# SingleBoardDrone_Pow.net
KiCad netlist of a schematic drawn in Altium Designer
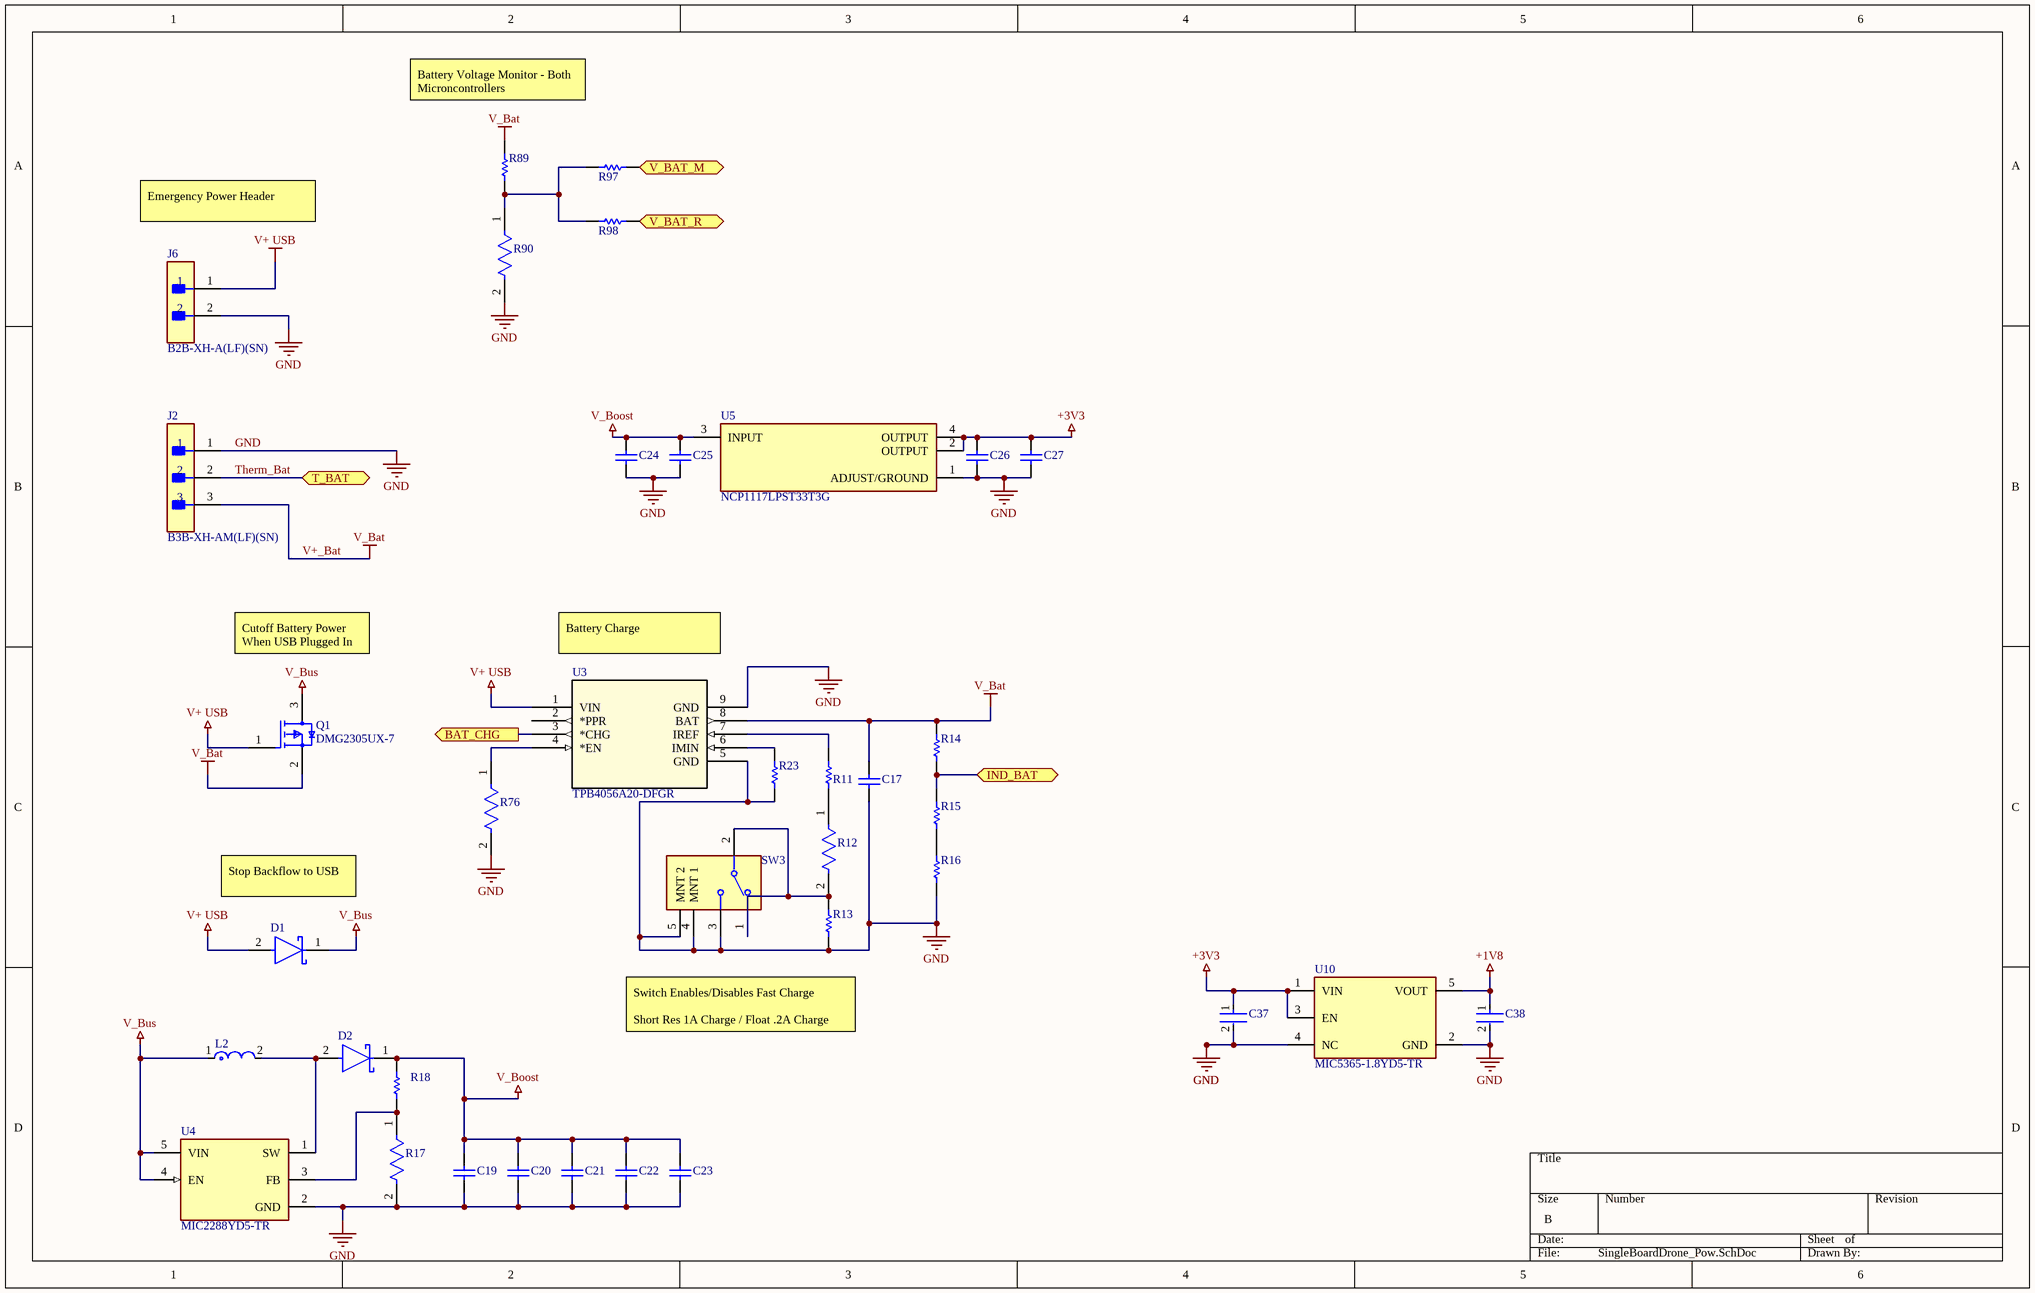
[diagram p0: SingleBoardDrone_Pow.SchDoc]

(export (version "E")
  (design (tool "Eeschema 10.0.6"))
  (components
    (comp (ref "C17")
      (value "CL10A475KQ8NNNC")
      (footprint "CAPC1608X90X30LL10T20")
      (description "Chip Capacitor, 4.7 uF, +/- 10%, 6.3 V, -55 to 85 degC, 0603 (1608 Metric), RoHS, Tape and Reel")
      (fields (field (name "MANUFACTURER") "Samsung Electro-Mechanics"))
      (libsource (lib "Altium Content Vault") (part "CAP-NP-2"))
    )
    (comp (ref "C19")
      (value "CL10A475KQ8NNNC")
      (footprint "CAPC1608X90X30LL10T20")
      (description "Chip Capacitor, 4.7 uF, +/- 10%, 6.3 V, -55 to 85 degC, 0603 (1608 Metric), RoHS, Tape and Reel")
      (fields (field (name "MANUFACTURER") "Samsung Electro-Mechanics"))
      (libsource (lib "Altium Content Vault") (part "CAP-NP-2"))
    )
    (comp (ref "C20")
      (value "CL10A475KQ8NNNC")
      (footprint "CAPC1608X90X30LL10T20")
      (description "Chip Capacitor, 4.7 uF, +/- 10%, 6.3 V, -55 to 85 degC, 0603 (1608 Metric), RoHS, Tape and Reel")
      (fields (field (name "MANUFACTURER") "Samsung Electro-Mechanics"))
      (libsource (lib "Altium Content Vault") (part "CAP-NP-2"))
    )
    (comp (ref "C21")
      (value "CL10A475KQ8NNNC")
      (footprint "CAPC1608X90X30LL10T20")
      (description "Chip Capacitor, 4.7 uF, +/- 10%, 6.3 V, -55 to 85 degC, 0603 (1608 Metric), RoHS, Tape and Reel")
      (fields (field (name "MANUFACTURER") "Samsung Electro-Mechanics"))
      (libsource (lib "Altium Content Vault") (part "CAP-NP-2"))
    )
    (comp (ref "C22")
      (value "CL10A475KQ8NNNC")
      (footprint "CAPC1608X90X30LL10T20")
      (description "Chip Capacitor, 4.7 uF, +/- 10%, 6.3 V, -55 to 85 degC, 0603 (1608 Metric), RoHS, Tape and Reel")
      (fields (field (name "MANUFACTURER") "Samsung Electro-Mechanics"))
      (libsource (lib "Altium Content Vault") (part "CAP-NP-2"))
    )
    (comp (ref "C23")
      (value "CL10A475KQ8NNNC")
      (footprint "CAPC1608X90X30LL10T20")
      (description "Chip Capacitor, 4.7 uF, +/- 10%, 6.3 V, -55 to 85 degC, 0603 (1608 Metric), RoHS, Tape and Reel")
      (fields (field (name "MANUFACTURER") "Samsung Electro-Mechanics"))
      (libsource (lib "Altium Content Vault") (part "CAP-NP-2"))
    )
    (comp (ref "C24")
      (value "CL10A475KQ8NNNC")
      (footprint "CAPC1608X90X30LL10T20")
      (description "Chip Capacitor, 4.7 uF, +/- 10%, 6.3 V, -55 to 85 degC, 0603 (1608 Metric), RoHS, Tape and Reel")
      (fields (field (name "MANUFACTURER") "Samsung Electro-Mechanics"))
      (libsource (lib "Altium Content Vault") (part "CAP-NP-2"))
    )
    (comp (ref "C25")
      (value "CL10A475KQ8NNNC")
      (footprint "CAPC1608X90X30LL10T20")
      (description "Chip Capacitor, 4.7 uF, +/- 10%, 6.3 V, -55 to 85 degC, 0603 (1608 Metric), RoHS, Tape and Reel")
      (fields (field (name "MANUFACTURER") "Samsung Electro-Mechanics"))
      (libsource (lib "Altium Content Vault") (part "CAP-NP-2"))
    )
    (comp (ref "C26")
      (value "CL10A475KQ8NNNC")
      (footprint "CAPC1608X90X30LL10T20")
      (description "Chip Capacitor, 4.7 uF, +/- 10%, 6.3 V, -55 to 85 degC, 0603 (1608 Metric), RoHS, Tape and Reel")
      (fields (field (name "MANUFACTURER") "Samsung Electro-Mechanics"))
      (libsource (lib "Altium Content Vault") (part "CAP-NP-2"))
    )
    (comp (ref "C27")
      (value "CL10A475KQ8NNNC")
      (footprint "CAPC1608X90X30LL10T20")
      (description "Chip Capacitor, 4.7 uF, +/- 10%, 6.3 V, -55 to 85 degC, 0603 (1608 Metric), RoHS, Tape and Reel")
      (fields (field (name "MANUFACTURER") "Samsung Electro-Mechanics"))
      (libsource (lib "Altium Content Vault") (part "CAP-NP-2"))
    )
    (comp (ref "C37")
      (value "CGA3E1X7R1E105K080AC")
      (footprint "FP-CGA3E-0_3-0_1-IPC_A")
      (description "Cap Ceramic 1uF 25V X7R 10% Pad SMD 0603 +125°C Automotive T/R")
      (fields (field (name "VOLTAGE") "25V") (field (name "TOLERANCE") "10%"))
      (libsource (lib "Altium Content Vault") (part "b4654b650e69147ec39a6b967a45e02"))
    )
    (comp (ref "C38")
      (value "CGA3E1X7R1E105K080AC")
      (footprint "FP-CGA3E-0_3-0_1-IPC_A")
      (description "Cap Ceramic 1uF 25V X7R 10% Pad SMD 0603 +125°C Automotive T/R")
      (fields (field (name "VOLTAGE") "25V") (field (name "TOLERANCE") "10%"))
      (libsource (lib "Altium Content Vault") (part "b4654b650e69147ec39a6b967a45e02"))
    )
    (comp (ref "D1")
      (value "PMEG3020DEP,115")
      (footprint "FP-SOD128-MFG")
      (description "DIODE SCHOTTKY 30V 2A SOD128")
      (libsource (lib "Altium Content Vault") (part "c1678fac7984e62e0809fbf79c06691"))
    )
    (comp (ref "D2")
      (value "PMEG3020DEP,115")
      (footprint "FP-SOD128-MFG")
      (description "DIODE SCHOTTKY 30V 2A SOD128")
      (libsource (lib "Altium Content Vault") (part "c1678fac7984e62e0809fbf79c06691"))
    )
    (comp (ref "J2")
      (value "B3B-XH-AM(LF)(SN)")
      (footprint "FP-B3B-XH-AM_LF_SN-MFG")
      (description "CONN HEADER VERT 3POS 2.5MM")
      (libsource (lib "Altium Content Vault") (part "0d3f023dd272f625e17a2be33dea85f"))
    )
    (comp (ref "J6")
      (value "B2B-XH-A(LF)(SN)")
      (footprint "FP-B2B-XH-A_LF_SN-MFG")
      (description "CONN HEADER VERT 2POS 2.5MM")
      (libsource (lib "Altium Content Vault") (part "3bc925449376181038e59eaffc5286c"))
    )
    (comp (ref "L2")
      (value "VLS5045EX-100M")
      (footprint "FP-VLS5045EX-100M-MFG")
      (description "FIXED IND 10UH 2.5A 79.3 MOHM")
      (fields (field (name "TOLERANCE") "20%"))
      (libsource (lib "Altium Content Vault") (part "4cc4b267dca4c8e51f7102f422741d8"))
    )
    (comp (ref "Q1")
      (value "DMG2305UX-7")
      (footprint "FP-SOT23-IPC_B")
      (description "MOSFET P-CH 20V 4.2A SOT23")
      (libsource (lib "Altium Content Vault") (part "87831b450059b469d4a68f5364f4496"))
    )
    (comp (ref "R11")
      (value "ERJ-6ENF2000V")
      (footprint "RESC2013X70X40ML20T20")
      (fields (field (name "MANUFACTURER") "Panasonic"))
      (libsource (lib "Altium Content Vault") (part "RES"))
    )
    (comp (ref "R12")
      (value "RMCF0402JT1K00")
      (footprint "FP-RMCF0402-IPC_B")
      (description "1kΩ ±5% 0.063W 0402 Thick Film Chip Resistor AEC-Q200 compliant")
      (fields (field (name "TOLERANCE") "5%"))
      (libsource (lib "Altium Content Vault") (part "1029c3af85768c4190bb7ad29bc67b5"))
    )
    (comp (ref "R13")
      (value "CRCW08055K00FKTA")
      (footprint "RESC2013X50X30ML20T20")
      (fields (field (name "MANUFACTURER") "Vishay Dale"))
      (libsource (lib "Altium Content Vault") (part "RES"))
    )
    (comp (ref "R14")
      (value "CRCW08055K00FKTA")
      (footprint "RESC2013X50X30ML20T20")
      (fields (field (name "MANUFACTURER") "Vishay Dale"))
      (libsource (lib "Altium Content Vault") (part "RES"))
    )
    (comp (ref "R15")
      (value "CRCW08055K00FKTA")
      (footprint "RESC2013X50X30ML20T20")
      (fields (field (name "MANUFACTURER") "Vishay Dale"))
      (libsource (lib "Altium Content Vault") (part "RES"))
    )
    (comp (ref "R16")
      (value "CRCW08055K00FKTA")
      (footprint "RESC2013X50X30ML20T20")
      (fields (field (name "MANUFACTURER") "Vishay Dale"))
      (libsource (lib "Altium Content Vault") (part "RES"))
    )
    (comp (ref "R17")
      (value "RMCF0402JT1K00")
      (footprint "FP-RMCF0402-IPC_B")
      (description "1kΩ ±5% 0.063W 0402 Thick Film Chip Resistor AEC-Q200 compliant")
      (fields (field (name "TOLERANCE") "5%"))
      (libsource (lib "Altium Content Vault") (part "1029c3af85768c4190bb7ad29bc67b5"))
    )
    (comp (ref "R18")
      (value "CRCW08055K00FKTA")
      (footprint "RESC2013X50X30ML20T20")
      (fields (field (name "MANUFACTURER") "Vishay Dale"))
      (libsource (lib "Altium Content Vault") (part "RES"))
    )
    (comp (ref "R23")
      (value "CRCW08055K00FKTA")
      (footprint "RESC2013X50X30ML20T20")
      (fields (field (name "MANUFACTURER") "Vishay Dale"))
      (libsource (lib "Altium Content Vault") (part "RES"))
    )
    (comp (ref "R76")
      (value "RC0402FR-070RL")
      (footprint "FP-RC0402-0_4-IPC_A")
      (description "RES SMD 0 OHM JUMPER 1/16W 0402")
      (fields (field (name "TOLERANCE") "1%"))
      (libsource (lib "Altium Content Vault") (part "1029c3af85768c4190bb7ad29bc67b5"))
    )
    (comp (ref "R89")
      (value "CRCW08055K00FKTA")
      (footprint "RESC2013X50X30ML20T20")
      (fields (field (name "MANUFACTURER") "Vishay Dale"))
      (libsource (lib "Altium Content Vault") (part "RES"))
    )
    (comp (ref "R90")
      (value "RMCF0603JG10K0")
      (footprint "FP-RMCF0603-MFG")
      (description "10kΩ ±5% 0.1W 0603 Thick Film Chip Resistor AEC-Q200 compliant")
      (fields (field (name "TOLERANCE") "5%"))
      (libsource (lib "Altium Content Vault") (part "1029c3af85768c4190bb7ad29bc67b5"))
    )
    (comp (ref "R97")
      (value "ERJ-6ENF2000V")
      (footprint "RESC2013X70X40ML20T20")
      (fields (field (name "MANUFACTURER") "Panasonic"))
      (libsource (lib "Altium Content Vault") (part "RES"))
    )
    (comp (ref "R98")
      (value "ERJ-6ENF2000V")
      (footprint "RESC2013X70X40ML20T20")
      (fields (field (name "MANUFACTURER") "Panasonic"))
      (libsource (lib "Altium Content Vault") (part "RES"))
    )
    (comp (ref "SW3")
      (value "1825232-1")
      (footprint "FP-1825232-1-MFG")
      (description "SWITCH SLIDE SPDT 200MA 30V")
      (fields
        (field (name "OCTOPART") "https://octopart.com/1825232-1-te+connectivity-45209882")
        (field (name "MANUFACTURER") "TE Connectivity")
      )
      (libsource (lib "Altium Content Vault") (part "b81b21e7de6c425a317152e587b8097"))
    )
    (comp (ref "U3")
      (value "TPB4056A20-DFGR")
      (footprint "TPB4056A20-DFGR:DFN2X2-8_TPK")
      (description "No Description Available")
      (fields (field (name "COPYRIGHT") "Copyright (C) 2025 Ultra Librarian. All rights reserved."))
      (libsource (lib "TPB4056A20-DFGR") (part "TPB4056A20-DFGR"))
    )
    (comp (ref "U4")
      (value "MIC2288YD5-TR")
      (footprint "FP-TSOT-5LD-PL-1-MFG")
      (description "IC REG BOOST ADJ 1.2A TSOT23-5")
      (libsource (lib "Altium Content Vault") (part "8b40e419ffb951c8150a61de73387bc"))
    )
    (comp (ref "U5")
      (value "NCP1117LPST33T3G")
      (footprint "FP-318H-MFG")
      (description "IC REG LINEAR 3.3V 1A SOT223")
      (libsource (lib "Altium Content Vault") (part "ba9dfc6f1948e29eb9591bef83395b3"))
    )
    (comp (ref "U10")
      (value "MIC5365-1.8YD5-TR")
      (footprint "FP-TSOT-5LD-PL-1-MFG")
      (description "MIC5365-1.8YD5-TR LDO Regulator Pos 1.8V 0.15A 5-Pin TSOT-23 T/R")
      (libsource (lib "Altium Content Vault") (part "49efecb8457b62bbb278fcbf558b656"))
    )
  )
  (nets
    (net (code "1") (name "+1V8") (class "Default")
      (node (ref "C38") (pin "1") (pinfunction "1_1") (pintype "passive"))
      (node (ref "U10") (pin "5") (pinfunction "VOUT_5") (pintype "passive"))
    )
    (net (code "2") (name "+3V3") (class "Default")
      (node (ref "C26") (pin "1") (pinfunction "1_1") (pintype "passive"))
      (node (ref "C27") (pin "1") (pinfunction "1_1") (pintype "passive"))
      (node (ref "C37") (pin "1") (pinfunction "1_1") (pintype "passive"))
      (node (ref "U10") (pin "1") (pinfunction "VIN_1") (pintype "power_in"))
      (node (ref "U10") (pin "3") (pinfunction "EN_3") (pintype "passive"))
      (node (ref "U5") (pin "2") (pinfunction "OUTPUT_2") (pintype "power_in"))
      (node (ref "U5") (pin "4") (pinfunction "OUTPUT_4") (pintype "power_in"))
    )
    (net (code "3") (name "/BAT_CHG") (class "Default")
      (node (ref "U3") (pin "3") (pinfunction "*CHG_3") (pintype "output"))
    )
    (net (code "4") (name "/IND_BAT") (class "Default")
      (node (ref "R14") (pin "2") (pinfunction "2_2") (pintype "passive"))
      (node (ref "R15") (pin "1") (pinfunction "1_1") (pintype "passive"))
    )
    (net (code "5") (name "/Therm_Bat") (class "Default")
      (node (ref "J2") (pin "2") (pinfunction "2_2") (pintype "passive"))
    )
    (net (code "6") (name "/V_BAT_M") (class "Default")
      (node (ref "R97") (pin "1") (pinfunction "1_1") (pintype "passive"))
    )
    (net (code "7") (name "/V_BAT_R") (class "Default")
      (node (ref "R98") (pin "1") (pinfunction "1_1") (pintype "passive"))
    )
    (net (code "8") (name "GND") (class "Default")
      (node (ref "C17") (pin "2") (pinfunction "2_2") (pintype "passive"))
      (node (ref "C19") (pin "2") (pinfunction "2_2") (pintype "passive"))
      (node (ref "C20") (pin "2") (pinfunction "2_2") (pintype "passive"))
      (node (ref "C21") (pin "2") (pinfunction "2_2") (pintype "passive"))
      (node (ref "C22") (pin "2") (pinfunction "2_2") (pintype "passive"))
      (node (ref "C23") (pin "2") (pinfunction "2_2") (pintype "passive"))
      (node (ref "C24") (pin "2") (pinfunction "2_2") (pintype "passive"))
      (node (ref "C25") (pin "2") (pinfunction "2_2") (pintype "passive"))
      (node (ref "C26") (pin "2") (pinfunction "2_2") (pintype "passive"))
      (node (ref "C27") (pin "2") (pinfunction "2_2") (pintype "passive"))
      (node (ref "C37") (pin "2") (pinfunction "2_2") (pintype "passive"))
      (node (ref "C38") (pin "2") (pinfunction "2_2") (pintype "passive"))
      (node (ref "J2") (pin "1") (pinfunction "1_1") (pintype "passive"))
      (node (ref "J6") (pin "2") (pinfunction "2_2") (pintype "passive"))
      (node (ref "R13") (pin "2") (pinfunction "2_2") (pintype "passive"))
      (node (ref "R16") (pin "2") (pinfunction "2_2") (pintype "passive"))
      (node (ref "R17") (pin "2") (pinfunction "2_2") (pintype "passive"))
      (node (ref "R23") (pin "2") (pinfunction "2_2") (pintype "passive"))
      (node (ref "R76") (pin "2") (pinfunction "2_2") (pintype "passive"))
      (node (ref "R90") (pin "2") (pinfunction "2_2") (pintype "passive"))
      (node (ref "SW3") (pin "3") (pinfunction "3_3") (pintype "passive"))
      (node (ref "SW3") (pin "4") (pinfunction "MNT_1_4") (pintype "passive"))
      (node (ref "SW3") (pin "5") (pinfunction "MNT_2_5") (pintype "passive"))
      (node (ref "U10") (pin "2") (pinfunction "GND_2") (pintype "power_in"))
      (node (ref "U10") (pin "4") (pinfunction "NC_4") (pintype "passive"))
      (node (ref "U3") (pin "5") (pinfunction "GND_5") (pintype "power_in"))
      (node (ref "U3") (pin "9") (pinfunction "GND_9") (pintype "power_in"))
      (node (ref "U4") (pin "2") (pinfunction "GND_2") (pintype "power_in"))
      (node (ref "U5") (pin "1") (pinfunction "ADJUST/GROUND_1") (pintype "power_in"))
    )
    (net (code "9") (name "Net-(D2-A)") (class "Default")
      (node (ref "D2") (pin "2") (pinfunction "A_2") (pintype "passive"))
      (node (ref "L2") (pin "2") (pinfunction "2_2") (pintype "passive"))
      (node (ref "U4") (pin "1") (pinfunction "SW_1") (pintype "power_in"))
    )
    (net (code "10") (name "Net-(R11-Pad2)") (class "Default")
      (node (ref "R11") (pin "2") (pinfunction "2_2") (pintype "passive"))
      (node (ref "R12") (pin "1") (pinfunction "1_1") (pintype "passive"))
    )
    (net (code "11") (name "Net-(R12-Pad2)") (class "Default")
      (node (ref "R12") (pin "2") (pinfunction "2_2") (pintype "passive"))
      (node (ref "R13") (pin "1") (pinfunction "1_1") (pintype "passive"))
      (node (ref "SW3") (pin "1") (pinfunction "1_1") (pintype "passive"))
      (node (ref "SW3") (pin "2") (pinfunction "2_2") (pintype "passive"))
    )
    (net (code "12") (name "Net-(R15-Pad2)") (class "Default")
      (node (ref "R15") (pin "2") (pinfunction "2_2") (pintype "passive"))
      (node (ref "R16") (pin "1") (pinfunction "1_1") (pintype "passive"))
    )
    (net (code "13") (name "Net-(R89-Pad2)") (class "Default")
      (node (ref "R89") (pin "2") (pinfunction "2_2") (pintype "passive"))
      (node (ref "R90") (pin "1") (pinfunction "1_1") (pintype "passive"))
      (node (ref "R97") (pin "2") (pinfunction "2_2") (pintype "passive"))
      (node (ref "R98") (pin "2") (pinfunction "2_2") (pintype "passive"))
    )
    (net (code "14") (name "Net-(U3-*EN)") (class "Default")
      (node (ref "R76") (pin "1") (pinfunction "1_1") (pintype "passive"))
      (node (ref "U3") (pin "4") (pinfunction "*EN_4") (pintype "input"))
    )
    (net (code "15") (name "Net-(U3-IMIN)") (class "Default")
      (node (ref "R23") (pin "1") (pinfunction "1_1") (pintype "passive"))
      (node (ref "U3") (pin "6") (pinfunction "IMIN_6") (pintype "input"))
    )
    (net (code "16") (name "Net-(U3-IREF)") (class "Default")
      (node (ref "R11") (pin "1") (pinfunction "1_1") (pintype "passive"))
      (node (ref "U3") (pin "7") (pinfunction "IREF_7") (pintype "input"))
    )
    (net (code "17") (name "Net-(U4-FB)") (class "Default")
      (node (ref "R17") (pin "1") (pinfunction "1_1") (pintype "passive"))
      (node (ref "R18") (pin "2") (pinfunction "2_2") (pintype "passive"))
      (node (ref "U4") (pin "3") (pinfunction "FB_3") (pintype "passive"))
    )
    (net (code "18") (name "V+ USB") (class "Default")
      (node (ref "D1") (pin "2") (pinfunction "A_2") (pintype "passive"))
      (node (ref "J6") (pin "1") (pinfunction "1_1") (pintype "passive"))
      (node (ref "Q1") (pin "1") (pinfunction "GATE_1") (pintype "passive"))
      (node (ref "U3") (pin "1") (pinfunction "VIN_1") (pintype "power_in"))
    )
    (net (code "19") (name "V_Bat") (class "Default")
      (node (ref "C17") (pin "1") (pinfunction "1_1") (pintype "passive"))
      (node (ref "J2") (pin "3") (pinfunction "3_3") (pintype "passive"))
      (node (ref "Q1") (pin "2") (pinfunction "SOURCE_2") (pintype "passive"))
      (node (ref "R14") (pin "1") (pinfunction "1_1") (pintype "passive"))
      (node (ref "R89") (pin "1") (pinfunction "1_1") (pintype "passive"))
      (node (ref "U3") (pin "8") (pinfunction "BAT_8") (pintype "output"))
    )
    (net (code "20") (name "V_Boost") (class "Default")
      (node (ref "C19") (pin "1") (pinfunction "1_1") (pintype "passive"))
      (node (ref "C20") (pin "1") (pinfunction "1_1") (pintype "passive"))
      (node (ref "C21") (pin "1") (pinfunction "1_1") (pintype "passive"))
      (node (ref "C22") (pin "1") (pinfunction "1_1") (pintype "passive"))
      (node (ref "C23") (pin "1") (pinfunction "1_1") (pintype "passive"))
      (node (ref "C24") (pin "1") (pinfunction "1_1") (pintype "passive"))
      (node (ref "C25") (pin "1") (pinfunction "1_1") (pintype "passive"))
      (node (ref "D2") (pin "1") (pinfunction "C_1") (pintype "passive"))
      (node (ref "R18") (pin "1") (pinfunction "1_1") (pintype "passive"))
      (node (ref "U5") (pin "3") (pinfunction "INPUT_3") (pintype "power_in"))
    )
    (net (code "21") (name "V_Bus") (class "Default")
      (node (ref "D1") (pin "1") (pinfunction "C_1") (pintype "passive"))
      (node (ref "L2") (pin "1") (pinfunction "1_1") (pintype "passive"))
      (node (ref "Q1") (pin "3") (pinfunction "DRAIN_3") (pintype "passive"))
      (node (ref "U4") (pin "4") (pinfunction "EN_4") (pintype "input"))
      (node (ref "U4") (pin "5") (pinfunction "VIN_5") (pintype "power_in"))
    )
    (net (code "22") (name "unconnected-(U3-*PPR-Pad2)") (class "Default")
      (node (ref "U3") (pin "2") (pinfunction "*PPR_2") (pintype "output"))
    )
  )
)
